# SCH_clavier_2026-02-09.net
KiCad netlist of a schematic drawn in EasyEDA
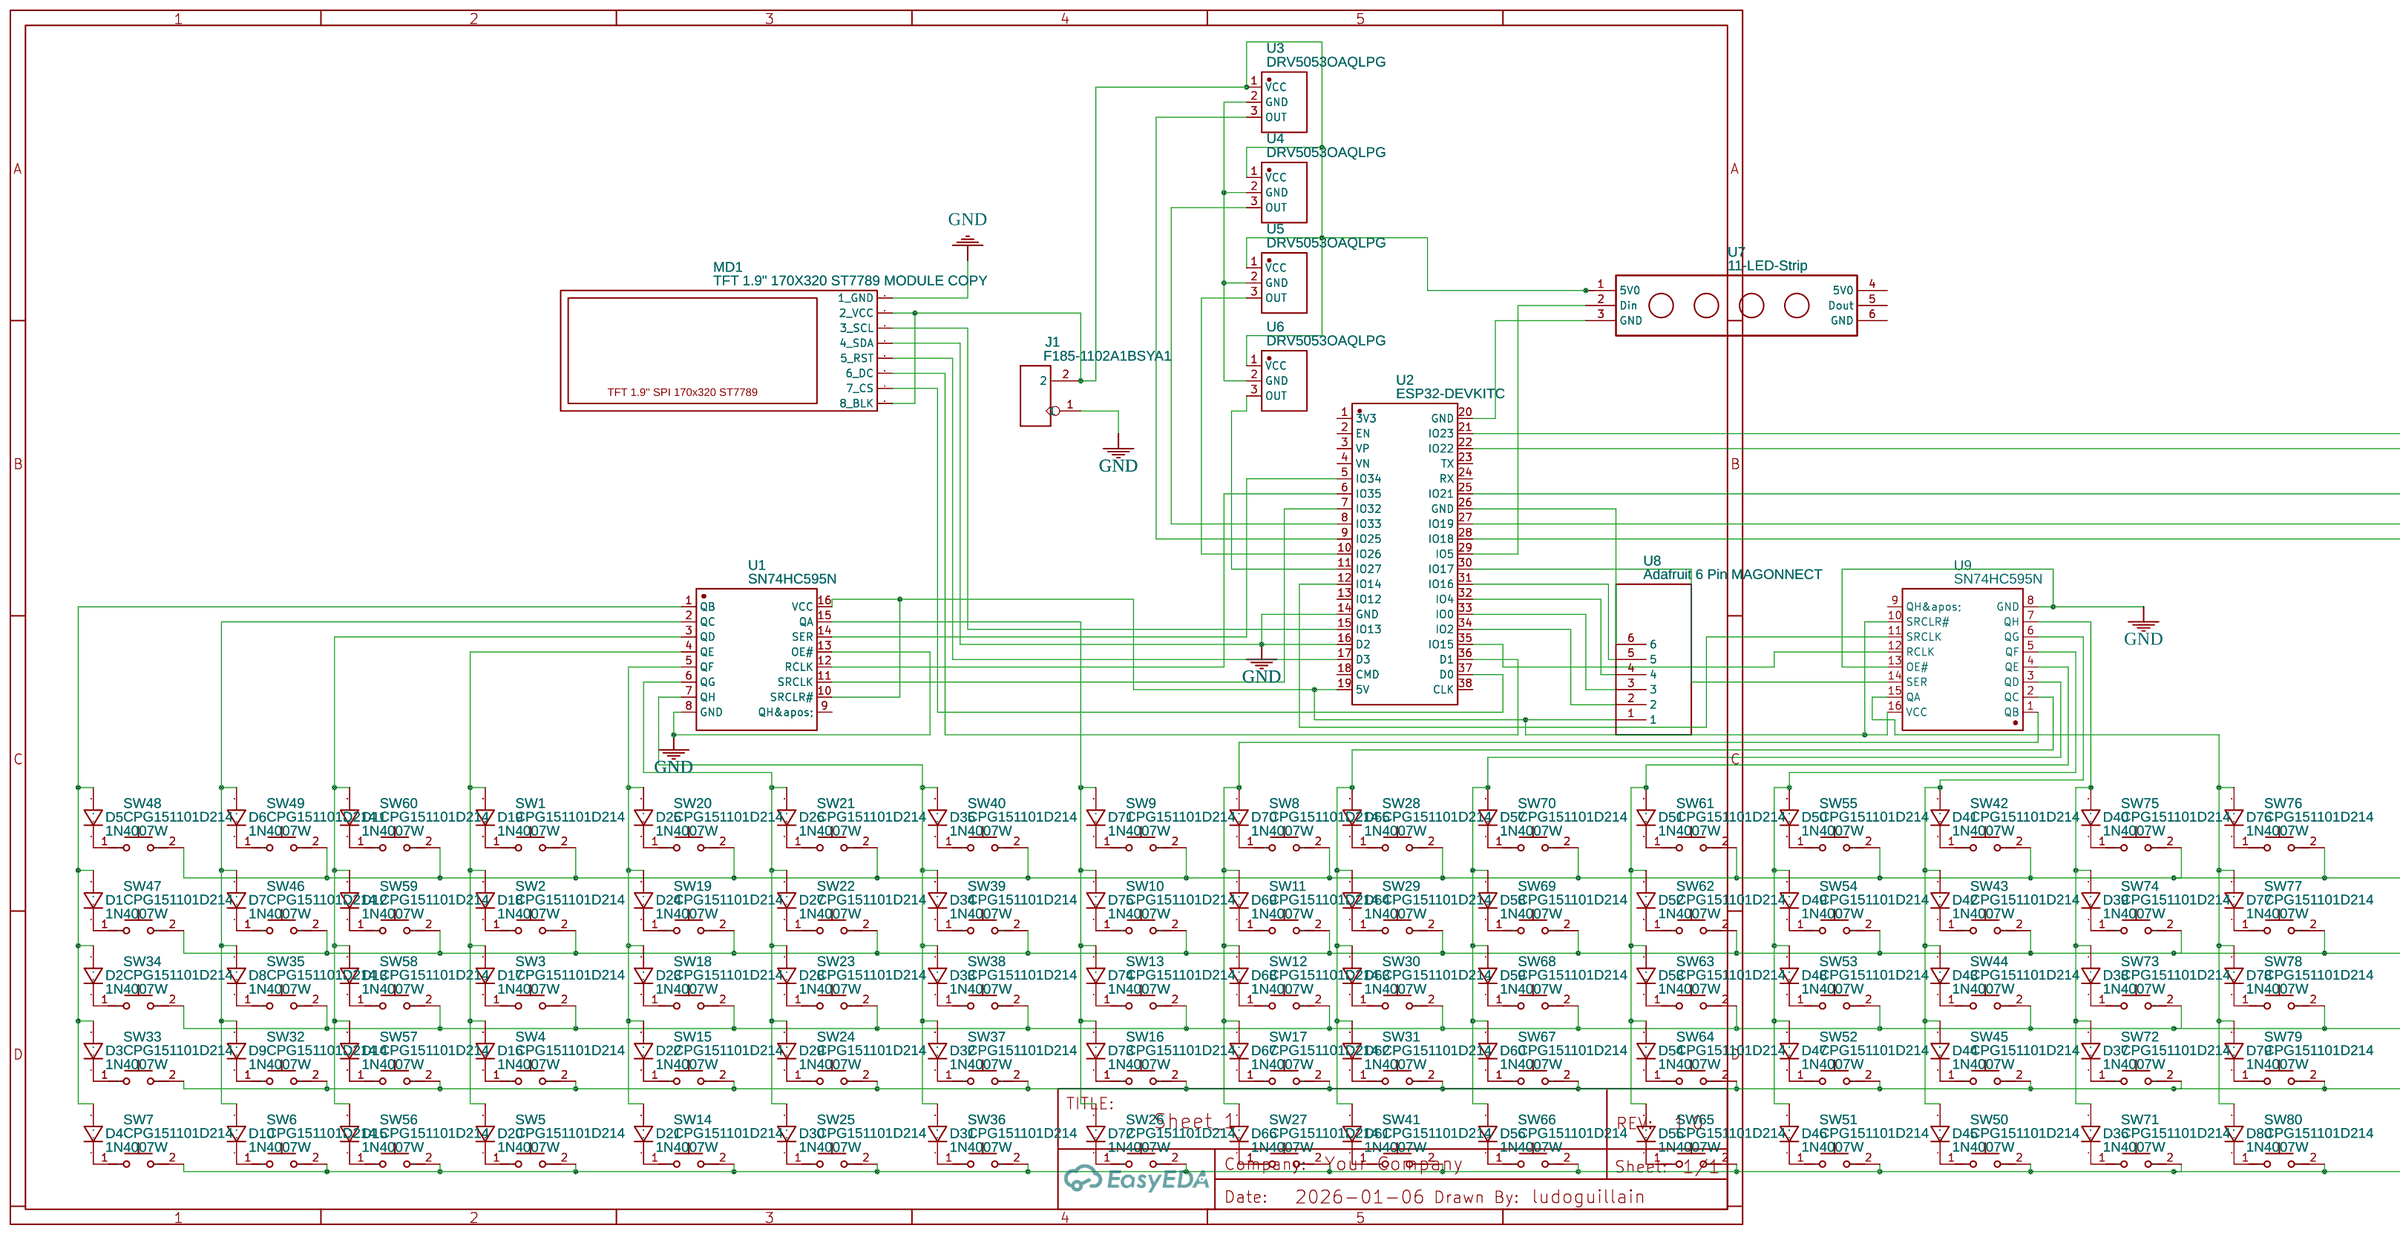
[diagram p0: schematic sheet]

(export (version "E")
  (design (tool "Eeschema 10.0.6"))
  (components
    (comp (ref "D1")
      (value "1N4007W")
      (fields (field (name "Manufacturer") "BLUE ROCKET"))
      (libsource (lib "") (part "1N4007W"))
    )
    (comp (ref "D2")
      (value "1N4007W")
      (fields (field (name "Manufacturer") "BLUE ROCKET"))
      (libsource (lib "") (part "1N4007W"))
    )
    (comp (ref "D3")
      (value "1N4007W")
      (fields (field (name "Manufacturer") "BLUE ROCKET"))
      (libsource (lib "") (part "1N4007W"))
    )
    (comp (ref "D4")
      (value "1N4007W")
      (fields (field (name "Manufacturer") "BLUE ROCKET"))
      (libsource (lib "") (part "1N4007W"))
    )
    (comp (ref "D5")
      (value "1N4007W")
      (fields (field (name "Manufacturer") "BLUE ROCKET"))
      (libsource (lib "") (part "1N4007W"))
    )
    (comp (ref "D6")
      (value "1N4007W")
      (fields (field (name "Manufacturer") "BLUE ROCKET"))
      (libsource (lib "") (part "1N4007W"))
    )
    (comp (ref "D7")
      (value "1N4007W")
      (fields (field (name "Manufacturer") "BLUE ROCKET"))
      (libsource (lib "") (part "1N4007W"))
    )
    (comp (ref "D8")
      (value "1N4007W")
      (fields (field (name "Manufacturer") "BLUE ROCKET"))
      (libsource (lib "") (part "1N4007W"))
    )
    (comp (ref "D9")
      (value "1N4007W")
      (fields (field (name "Manufacturer") "BLUE ROCKET"))
      (libsource (lib "") (part "1N4007W"))
    )
    (comp (ref "D10")
      (value "1N4007W")
      (fields (field (name "Manufacturer") "BLUE ROCKET"))
      (libsource (lib "") (part "1N4007W"))
    )
    (comp (ref "D11")
      (value "1N4007W")
      (fields (field (name "Manufacturer") "BLUE ROCKET"))
      (libsource (lib "") (part "1N4007W"))
    )
    (comp (ref "D12")
      (value "1N4007W")
      (fields (field (name "Manufacturer") "BLUE ROCKET"))
      (libsource (lib "") (part "1N4007W"))
    )
    (comp (ref "D13")
      (value "1N4007W")
      (fields (field (name "Manufacturer") "BLUE ROCKET"))
      (libsource (lib "") (part "1N4007W"))
    )
    (comp (ref "D14")
      (value "1N4007W")
      (fields (field (name "Manufacturer") "BLUE ROCKET"))
      (libsource (lib "") (part "1N4007W"))
    )
    (comp (ref "D15")
      (value "1N4007W")
      (fields (field (name "Manufacturer") "BLUE ROCKET"))
      (libsource (lib "") (part "1N4007W"))
    )
    (comp (ref "D16")
      (value "1N4007W")
      (fields (field (name "Manufacturer") "BLUE ROCKET"))
      (libsource (lib "") (part "1N4007W"))
    )
    (comp (ref "D17")
      (value "1N4007W")
      (fields (field (name "Manufacturer") "BLUE ROCKET"))
      (libsource (lib "") (part "1N4007W"))
    )
    (comp (ref "D18")
      (value "1N4007W")
      (fields (field (name "Manufacturer") "BLUE ROCKET"))
      (libsource (lib "") (part "1N4007W"))
    )
    (comp (ref "D19")
      (value "1N4007W")
      (fields (field (name "Manufacturer") "BLUE ROCKET"))
      (libsource (lib "") (part "1N4007W"))
    )
    (comp (ref "D20")
      (value "1N4007W")
      (fields (field (name "Manufacturer") "BLUE ROCKET"))
      (libsource (lib "") (part "1N4007W"))
    )
    (comp (ref "D21")
      (value "1N4007W")
      (fields (field (name "Manufacturer") "BLUE ROCKET"))
      (libsource (lib "") (part "1N4007W"))
    )
    (comp (ref "D22")
      (value "1N4007W")
      (fields (field (name "Manufacturer") "BLUE ROCKET"))
      (libsource (lib "") (part "1N4007W"))
    )
    (comp (ref "D23")
      (value "1N4007W")
      (fields (field (name "Manufacturer") "BLUE ROCKET"))
      (libsource (lib "") (part "1N4007W"))
    )
    (comp (ref "D24")
      (value "1N4007W")
      (fields (field (name "Manufacturer") "BLUE ROCKET"))
      (libsource (lib "") (part "1N4007W"))
    )
    (comp (ref "D25")
      (value "1N4007W")
      (fields (field (name "Manufacturer") "BLUE ROCKET"))
      (libsource (lib "") (part "1N4007W"))
    )
    (comp (ref "D26")
      (value "1N4007W")
      (fields (field (name "Manufacturer") "BLUE ROCKET"))
      (libsource (lib "") (part "1N4007W"))
    )
    (comp (ref "D27")
      (value "1N4007W")
      (fields (field (name "Manufacturer") "BLUE ROCKET"))
      (libsource (lib "") (part "1N4007W"))
    )
    (comp (ref "D28")
      (value "1N4007W")
      (fields (field (name "Manufacturer") "BLUE ROCKET"))
      (libsource (lib "") (part "1N4007W"))
    )
    (comp (ref "D29")
      (value "1N4007W")
      (fields (field (name "Manufacturer") "BLUE ROCKET"))
      (libsource (lib "") (part "1N4007W"))
    )
    (comp (ref "D30")
      (value "1N4007W")
      (fields (field (name "Manufacturer") "BLUE ROCKET"))
      (libsource (lib "") (part "1N4007W"))
    )
    (comp (ref "D31")
      (value "1N4007W")
      (fields (field (name "Manufacturer") "BLUE ROCKET"))
      (libsource (lib "") (part "1N4007W"))
    )
    (comp (ref "D32")
      (value "1N4007W")
      (fields (field (name "Manufacturer") "BLUE ROCKET"))
      (libsource (lib "") (part "1N4007W"))
    )
    (comp (ref "D33")
      (value "1N4007W")
      (fields (field (name "Manufacturer") "BLUE ROCKET"))
      (libsource (lib "") (part "1N4007W"))
    )
    (comp (ref "D34")
      (value "1N4007W")
      (fields (field (name "Manufacturer") "BLUE ROCKET"))
      (libsource (lib "") (part "1N4007W"))
    )
    (comp (ref "D35")
      (value "1N4007W")
      (fields (field (name "Manufacturer") "BLUE ROCKET"))
      (libsource (lib "") (part "1N4007W"))
    )
    (comp (ref "D36")
      (value "1N4007W")
      (fields (field (name "Manufacturer") "BLUE ROCKET"))
      (libsource (lib "") (part "1N4007W"))
    )
    (comp (ref "D37")
      (value "1N4007W")
      (fields (field (name "Manufacturer") "BLUE ROCKET"))
      (libsource (lib "") (part "1N4007W"))
    )
    (comp (ref "D38")
      (value "1N4007W")
      (fields (field (name "Manufacturer") "BLUE ROCKET"))
      (libsource (lib "") (part "1N4007W"))
    )
    (comp (ref "D39")
      (value "1N4007W")
      (fields (field (name "Manufacturer") "BLUE ROCKET"))
      (libsource (lib "") (part "1N4007W"))
    )
    (comp (ref "D40")
      (value "1N4007W")
      (fields (field (name "Manufacturer") "BLUE ROCKET"))
      (libsource (lib "") (part "1N4007W"))
    )
    (comp (ref "D41")
      (value "1N4007W")
      (fields (field (name "Manufacturer") "BLUE ROCKET"))
      (libsource (lib "") (part "1N4007W"))
    )
    (comp (ref "D42")
      (value "1N4007W")
      (fields (field (name "Manufacturer") "BLUE ROCKET"))
      (libsource (lib "") (part "1N4007W"))
    )
    (comp (ref "D43")
      (value "1N4007W")
      (fields (field (name "Manufacturer") "BLUE ROCKET"))
      (libsource (lib "") (part "1N4007W"))
    )
    (comp (ref "D44")
      (value "1N4007W")
      (fields (field (name "Manufacturer") "BLUE ROCKET"))
      (libsource (lib "") (part "1N4007W"))
    )
    (comp (ref "D45")
      (value "1N4007W")
      (fields (field (name "Manufacturer") "BLUE ROCKET"))
      (libsource (lib "") (part "1N4007W"))
    )
    (comp (ref "D46")
      (value "1N4007W")
      (fields (field (name "Manufacturer") "BLUE ROCKET"))
      (libsource (lib "") (part "1N4007W"))
    )
    (comp (ref "D47")
      (value "1N4007W")
      (fields (field (name "Manufacturer") "BLUE ROCKET"))
      (libsource (lib "") (part "1N4007W"))
    )
    (comp (ref "D48")
      (value "1N4007W")
      (fields (field (name "Manufacturer") "BLUE ROCKET"))
      (libsource (lib "") (part "1N4007W"))
    )
    (comp (ref "D49")
      (value "1N4007W")
      (fields (field (name "Manufacturer") "BLUE ROCKET"))
      (libsource (lib "") (part "1N4007W"))
    )
    (comp (ref "D50")
      (value "1N4007W")
      (fields (field (name "Manufacturer") "BLUE ROCKET"))
      (libsource (lib "") (part "1N4007W"))
    )
    (comp (ref "D51")
      (value "1N4007W")
      (fields (field (name "Manufacturer") "BLUE ROCKET"))
      (libsource (lib "") (part "1N4007W"))
    )
    (comp (ref "D52")
      (value "1N4007W")
      (fields (field (name "Manufacturer") "BLUE ROCKET"))
      (libsource (lib "") (part "1N4007W"))
    )
    (comp (ref "D53")
      (value "1N4007W")
      (fields (field (name "Manufacturer") "BLUE ROCKET"))
      (libsource (lib "") (part "1N4007W"))
    )
    (comp (ref "D54")
      (value "1N4007W")
      (fields (field (name "Manufacturer") "BLUE ROCKET"))
      (libsource (lib "") (part "1N4007W"))
    )
    (comp (ref "D55")
      (value "1N4007W")
      (fields (field (name "Manufacturer") "BLUE ROCKET"))
      (libsource (lib "") (part "1N4007W"))
    )
    (comp (ref "D56")
      (value "1N4007W")
      (fields (field (name "Manufacturer") "BLUE ROCKET"))
      (libsource (lib "") (part "1N4007W"))
    )
    (comp (ref "D57")
      (value "1N4007W")
      (fields (field (name "Manufacturer") "BLUE ROCKET"))
      (libsource (lib "") (part "1N4007W"))
    )
    (comp (ref "D58")
      (value "1N4007W")
      (fields (field (name "Manufacturer") "BLUE ROCKET"))
      (libsource (lib "") (part "1N4007W"))
    )
    (comp (ref "D59")
      (value "1N4007W")
      (fields (field (name "Manufacturer") "BLUE ROCKET"))
      (libsource (lib "") (part "1N4007W"))
    )
    (comp (ref "D60")
      (value "1N4007W")
      (fields (field (name "Manufacturer") "BLUE ROCKET"))
      (libsource (lib "") (part "1N4007W"))
    )
    (comp (ref "D61")
      (value "1N4007W")
      (fields (field (name "Manufacturer") "BLUE ROCKET"))
      (libsource (lib "") (part "1N4007W"))
    )
    (comp (ref "D62")
      (value "1N4007W")
      (fields (field (name "Manufacturer") "BLUE ROCKET"))
      (libsource (lib "") (part "1N4007W"))
    )
    (comp (ref "D63")
      (value "1N4007W")
      (fields (field (name "Manufacturer") "BLUE ROCKET"))
      (libsource (lib "") (part "1N4007W"))
    )
    (comp (ref "D64")
      (value "1N4007W")
      (fields (field (name "Manufacturer") "BLUE ROCKET"))
      (libsource (lib "") (part "1N4007W"))
    )
    (comp (ref "D65")
      (value "1N4007W")
      (fields (field (name "Manufacturer") "BLUE ROCKET"))
      (libsource (lib "") (part "1N4007W"))
    )
    (comp (ref "D66")
      (value "1N4007W")
      (fields (field (name "Manufacturer") "BLUE ROCKET"))
      (libsource (lib "") (part "1N4007W"))
    )
    (comp (ref "D67")
      (value "1N4007W")
      (fields (field (name "Manufacturer") "BLUE ROCKET"))
      (libsource (lib "") (part "1N4007W"))
    )
    (comp (ref "D68")
      (value "1N4007W")
      (fields (field (name "Manufacturer") "BLUE ROCKET"))
      (libsource (lib "") (part "1N4007W"))
    )
    (comp (ref "D69")
      (value "1N4007W")
      (fields (field (name "Manufacturer") "BLUE ROCKET"))
      (libsource (lib "") (part "1N4007W"))
    )
    (comp (ref "D70")
      (value "1N4007W")
      (fields (field (name "Manufacturer") "BLUE ROCKET"))
      (libsource (lib "") (part "1N4007W"))
    )
    (comp (ref "D71")
      (value "1N4007W")
      (fields (field (name "Manufacturer") "BLUE ROCKET"))
      (libsource (lib "") (part "1N4007W"))
    )
    (comp (ref "D72")
      (value "1N4007W")
      (fields (field (name "Manufacturer") "BLUE ROCKET"))
      (libsource (lib "") (part "1N4007W"))
    )
    (comp (ref "D73")
      (value "1N4007W")
      (fields (field (name "Manufacturer") "BLUE ROCKET"))
      (libsource (lib "") (part "1N4007W"))
    )
    (comp (ref "D74")
      (value "1N4007W")
      (fields (field (name "Manufacturer") "BLUE ROCKET"))
      (libsource (lib "") (part "1N4007W"))
    )
    (comp (ref "D75")
      (value "1N4007W")
      (fields (field (name "Manufacturer") "BLUE ROCKET"))
      (libsource (lib "") (part "1N4007W"))
    )
    (comp (ref "D76")
      (value "1N4007W")
      (fields (field (name "Manufacturer") "BLUE ROCKET"))
      (libsource (lib "") (part "1N4007W"))
    )
    (comp (ref "D77")
      (value "1N4007W")
      (fields (field (name "Manufacturer") "BLUE ROCKET"))
      (libsource (lib "") (part "1N4007W"))
    )
    (comp (ref "D78")
      (value "1N4007W")
      (fields (field (name "Manufacturer") "BLUE ROCKET"))
      (libsource (lib "") (part "1N4007W"))
    )
    (comp (ref "D79")
      (value "1N4007W")
      (fields (field (name "Manufacturer") "BLUE ROCKET"))
      (libsource (lib "") (part "1N4007W"))
    )
    (comp (ref "D80")
      (value "1N4007W")
      (fields (field (name "Manufacturer") "BLUE ROCKET"))
      (libsource (lib "") (part "1N4007W"))
    )
    (comp (ref "J1") (value "F185-1102A1BSYA1") (libsource (lib "") (part "F185-1102A1BSYA1")))
    (comp (ref "MD1")
      (value "TFT 1.9\" 170X320 ST7789 MODULE COPY")
      (libsource (lib "") (part "TFT 1.9{dblquote} 170X320 ST7789 MODULE COPY"))
    )
    (comp (ref "SW1")
      (value "CPG151101D214")
      (fields (field (name "Manufacturer") "Kailh(凯华)"))
      (libsource (lib "") (part "CPG151101D214"))
    )
    (comp (ref "SW2")
      (value "CPG151101D214")
      (fields (field (name "Manufacturer") "Kailh(凯华)"))
      (libsource (lib "") (part "CPG151101D214"))
    )
    (comp (ref "SW3")
      (value "CPG151101D214")
      (fields (field (name "Manufacturer") "Kailh(凯华)"))
      (libsource (lib "") (part "CPG151101D214"))
    )
    (comp (ref "SW4")
      (value "CPG151101D214")
      (fields (field (name "Manufacturer") "Kailh(凯华)"))
      (libsource (lib "") (part "CPG151101D214"))
    )
    (comp (ref "SW5")
      (value "CPG151101D214")
      (fields (field (name "Manufacturer") "Kailh(凯华)"))
      (libsource (lib "") (part "CPG151101D214"))
    )
    (comp (ref "SW6")
      (value "CPG151101D214")
      (fields (field (name "Manufacturer") "Kailh(凯华)"))
      (libsource (lib "") (part "CPG151101D214"))
    )
    (comp (ref "SW7")
      (value "CPG151101D214")
      (fields (field (name "Manufacturer") "Kailh(凯华)"))
      (libsource (lib "") (part "CPG151101D214"))
    )
    (comp (ref "SW8")
      (value "CPG151101D214")
      (fields (field (name "Manufacturer") "Kailh(凯华)"))
      (libsource (lib "") (part "CPG151101D214"))
    )
    (comp (ref "SW9")
      (value "CPG151101D214")
      (fields (field (name "Manufacturer") "Kailh(凯华)"))
      (libsource (lib "") (part "CPG151101D214"))
    )
    (comp (ref "SW10")
      (value "CPG151101D214")
      (fields (field (name "Manufacturer") "Kailh(凯华)"))
      (libsource (lib "") (part "CPG151101D214"))
    )
    (comp (ref "SW11")
      (value "CPG151101D214")
      (fields (field (name "Manufacturer") "Kailh(凯华)"))
      (libsource (lib "") (part "CPG151101D214"))
    )
    (comp (ref "SW12")
      (value "CPG151101D214")
      (fields (field (name "Manufacturer") "Kailh(凯华)"))
      (libsource (lib "") (part "CPG151101D214"))
    )
    (comp (ref "SW13")
      (value "CPG151101D214")
      (fields (field (name "Manufacturer") "Kailh(凯华)"))
      (libsource (lib "") (part "CPG151101D214"))
    )
    (comp (ref "SW14")
      (value "CPG151101D214")
      (fields (field (name "Manufacturer") "Kailh(凯华)"))
      (libsource (lib "") (part "CPG151101D214"))
    )
    (comp (ref "SW15")
      (value "CPG151101D214")
      (fields (field (name "Manufacturer") "Kailh(凯华)"))
      (libsource (lib "") (part "CPG151101D214"))
    )
    (comp (ref "SW16")
      (value "CPG151101D214")
      (fields (field (name "Manufacturer") "Kailh(凯华)"))
      (libsource (lib "") (part "CPG151101D214"))
    )
    (comp (ref "SW17")
      (value "CPG151101D214")
      (fields (field (name "Manufacturer") "Kailh(凯华)"))
      (libsource (lib "") (part "CPG151101D214"))
    )
    (comp (ref "SW18")
      (value "CPG151101D214")
      (fields (field (name "Manufacturer") "Kailh(凯华)"))
      (libsource (lib "") (part "CPG151101D214"))
    )
    (comp (ref "SW19")
      (value "CPG151101D214")
      (fields (field (name "Manufacturer") "Kailh(凯华)"))
      (libsource (lib "") (part "CPG151101D214"))
    )
    (comp (ref "SW20")
      (value "CPG151101D214")
      (fields (field (name "Manufacturer") "Kailh(凯华)"))
      (libsource (lib "") (part "CPG151101D214"))
    )
    (comp (ref "SW21")
      (value "CPG151101D214")
      (fields (field (name "Manufacturer") "Kailh(凯华)"))
      (libsource (lib "") (part "CPG151101D214"))
    )
    (comp (ref "SW22")
      (value "CPG151101D214")
      (fields (field (name "Manufacturer") "Kailh(凯华)"))
      (libsource (lib "") (part "CPG151101D214"))
    )
    (comp (ref "SW23")
      (value "CPG151101D214")
      (fields (field (name "Manufacturer") "Kailh(凯华)"))
      (libsource (lib "") (part "CPG151101D214"))
    )
    (comp (ref "SW24")
      (value "CPG151101D214")
      (fields (field (name "Manufacturer") "Kailh(凯华)"))
      (libsource (lib "") (part "CPG151101D214"))
    )
    (comp (ref "SW25")
      (value "CPG151101D214")
      (fields (field (name "Manufacturer") "Kailh(凯华)"))
      (libsource (lib "") (part "CPG151101D214"))
    )
    (comp (ref "SW26")
      (value "CPG151101D214")
      (fields (field (name "Manufacturer") "Kailh(凯华)"))
      (libsource (lib "") (part "CPG151101D214"))
    )
    (comp (ref "SW27")
      (value "CPG151101D214")
      (fields (field (name "Manufacturer") "Kailh(凯华)"))
      (libsource (lib "") (part "CPG151101D214"))
    )
    (comp (ref "SW28")
      (value "CPG151101D214")
      (fields (field (name "Manufacturer") "Kailh(凯华)"))
      (libsource (lib "") (part "CPG151101D214"))
    )
    (comp (ref "SW29")
      (value "CPG151101D214")
      (fields (field (name "Manufacturer") "Kailh(凯华)"))
      (libsource (lib "") (part "CPG151101D214"))
    )
    (comp (ref "SW30")
      (value "CPG151101D214")
      (fields (field (name "Manufacturer") "Kailh(凯华)"))
      (libsource (lib "") (part "CPG151101D214"))
    )
    (comp (ref "SW31")
      (value "CPG151101D214")
      (fields (field (name "Manufacturer") "Kailh(凯华)"))
      (libsource (lib "") (part "CPG151101D214"))
    )
    (comp (ref "SW32")
      (value "CPG151101D214")
      (fields (field (name "Manufacturer") "Kailh(凯华)"))
      (libsource (lib "") (part "CPG151101D214"))
    )
    (comp (ref "SW33")
      (value "CPG151101D214")
      (fields (field (name "Manufacturer") "Kailh(凯华)"))
      (libsource (lib "") (part "CPG151101D214"))
    )
    (comp (ref "SW34")
      (value "CPG151101D214")
      (fields (field (name "Manufacturer") "Kailh(凯华)"))
      (libsource (lib "") (part "CPG151101D214"))
    )
    (comp (ref "SW35")
      (value "CPG151101D214")
      (fields (field (name "Manufacturer") "Kailh(凯华)"))
      (libsource (lib "") (part "CPG151101D214"))
    )
    (comp (ref "SW36")
      (value "CPG151101D214")
      (fields (field (name "Manufacturer") "Kailh(凯华)"))
      (libsource (lib "") (part "CPG151101D214"))
    )
    (comp (ref "SW37")
      (value "CPG151101D214")
      (fields (field (name "Manufacturer") "Kailh(凯华)"))
      (libsource (lib "") (part "CPG151101D214"))
    )
    (comp (ref "SW38")
      (value "CPG151101D214")
      (fields (field (name "Manufacturer") "Kailh(凯华)"))
      (libsource (lib "") (part "CPG151101D214"))
    )
    (comp (ref "SW39")
      (value "CPG151101D214")
      (fields (field (name "Manufacturer") "Kailh(凯华)"))
      (libsource (lib "") (part "CPG151101D214"))
    )
    (comp (ref "SW40")
      (value "CPG151101D214")
      (fields (field (name "Manufacturer") "Kailh(凯华)"))
      (libsource (lib "") (part "CPG151101D214"))
    )
    (comp (ref "SW41")
      (value "CPG151101D214")
      (fields (field (name "Manufacturer") "Kailh(凯华)"))
      (libsource (lib "") (part "CPG151101D214"))
    )
    (comp (ref "SW42")
      (value "CPG151101D214")
      (fields (field (name "Manufacturer") "Kailh(凯华)"))
      (libsource (lib "") (part "CPG151101D214"))
    )
    (comp (ref "SW43")
      (value "CPG151101D214")
      (fields (field (name "Manufacturer") "Kailh(凯华)"))
      (libsource (lib "") (part "CPG151101D214"))
    )
    (comp (ref "SW44")
      (value "CPG151101D214")
      (fields (field (name "Manufacturer") "Kailh(凯华)"))
      (libsource (lib "") (part "CPG151101D214"))
    )
    (comp (ref "SW45")
      (value "CPG151101D214")
      (fields (field (name "Manufacturer") "Kailh(凯华)"))
      (libsource (lib "") (part "CPG151101D214"))
    )
    (comp (ref "SW46")
      (value "CPG151101D214")
      (fields (field (name "Manufacturer") "Kailh(凯华)"))
      (libsource (lib "") (part "CPG151101D214"))
    )
    (comp (ref "SW47")
      (value "CPG151101D214")
      (fields (field (name "Manufacturer") "Kailh(凯华)"))
      (libsource (lib "") (part "CPG151101D214"))
    )
    (comp (ref "SW48")
      (value "CPG151101D214")
      (fields (field (name "Manufacturer") "Kailh(凯华)"))
      (libsource (lib "") (part "CPG151101D214"))
    )
    (comp (ref "SW49")
      (value "CPG151101D214")
      (fields (field (name "Manufacturer") "Kailh(凯华)"))
      (libsource (lib "") (part "CPG151101D214"))
    )
    (comp (ref "SW50")
      (value "CPG151101D214")
      (fields (field (name "Manufacturer") "Kailh(凯华)"))
      (libsource (lib "") (part "CPG151101D214"))
    )
    (comp (ref "SW51")
      (value "CPG151101D214")
      (fields (field (name "Manufacturer") "Kailh(凯华)"))
      (libsource (lib "") (part "CPG151101D214"))
    )
    (comp (ref "SW52")
      (value "CPG151101D214")
      (fields (field (name "Manufacturer") "Kailh(凯华)"))
      (libsource (lib "") (part "CPG151101D214"))
    )
    (comp (ref "SW53")
      (value "CPG151101D214")
      (fields (field (name "Manufacturer") "Kailh(凯华)"))
      (libsource (lib "") (part "CPG151101D214"))
    )
    (comp (ref "SW54")
      (value "CPG151101D214")
      (fields (field (name "Manufacturer") "Kailh(凯华)"))
      (libsource (lib "") (part "CPG151101D214"))
    )
    (comp (ref "SW55")
      (value "CPG151101D214")
      (fields (field (name "Manufacturer") "Kailh(凯华)"))
      (libsource (lib "") (part "CPG151101D214"))
    )
    (comp (ref "SW56")
      (value "CPG151101D214")
      (fields (field (name "Manufacturer") "Kailh(凯华)"))
      (libsource (lib "") (part "CPG151101D214"))
    )
    (comp (ref "SW57")
      (value "CPG151101D214")
      (fields (field (name "Manufacturer") "Kailh(凯华)"))
      (libsource (lib "") (part "CPG151101D214"))
    )
    (comp (ref "SW58")
      (value "CPG151101D214")
      (fields (field (name "Manufacturer") "Kailh(凯华)"))
      (libsource (lib "") (part "CPG151101D214"))
    )
    (comp (ref "SW59")
      (value "CPG151101D214")
      (fields (field (name "Manufacturer") "Kailh(凯华)"))
      (libsource (lib "") (part "CPG151101D214"))
    )
    (comp (ref "SW60")
      (value "CPG151101D214")
      (fields (field (name "Manufacturer") "Kailh(凯华)"))
      (libsource (lib "") (part "CPG151101D214"))
    )
    (comp (ref "SW61")
      (value "CPG151101D214")
      (fields (field (name "Manufacturer") "Kailh(凯华)"))
      (libsource (lib "") (part "CPG151101D214"))
    )
    (comp (ref "SW62")
      (value "CPG151101D214")
      (fields (field (name "Manufacturer") "Kailh(凯华)"))
      (libsource (lib "") (part "CPG151101D214"))
    )
    (comp (ref "SW63")
      (value "CPG151101D214")
      (fields (field (name "Manufacturer") "Kailh(凯华)"))
      (libsource (lib "") (part "CPG151101D214"))
    )
    (comp (ref "SW64")
      (value "CPG151101D214")
      (fields (field (name "Manufacturer") "Kailh(凯华)"))
      (libsource (lib "") (part "CPG151101D214"))
    )
    (comp (ref "SW65")
      (value "CPG151101D214")
      (fields (field (name "Manufacturer") "Kailh(凯华)"))
      (libsource (lib "") (part "CPG151101D214"))
    )
    (comp (ref "SW66")
      (value "CPG151101D214")
      (fields (field (name "Manufacturer") "Kailh(凯华)"))
      (libsource (lib "") (part "CPG151101D214"))
    )
    (comp (ref "SW67")
      (value "CPG151101D214")
      (fields (field (name "Manufacturer") "Kailh(凯华)"))
      (libsource (lib "") (part "CPG151101D214"))
    )
    (comp (ref "SW68")
      (value "CPG151101D214")
      (fields (field (name "Manufacturer") "Kailh(凯华)"))
      (libsource (lib "") (part "CPG151101D214"))
    )
    (comp (ref "SW69")
      (value "CPG151101D214")
      (fields (field (name "Manufacturer") "Kailh(凯华)"))
      (libsource (lib "") (part "CPG151101D214"))
    )
    (comp (ref "SW70")
      (value "CPG151101D214")
      (fields (field (name "Manufacturer") "Kailh(凯华)"))
      (libsource (lib "") (part "CPG151101D214"))
    )
    (comp (ref "SW71")
      (value "CPG151101D214")
      (fields (field (name "Manufacturer") "Kailh(凯华)"))
      (libsource (lib "") (part "CPG151101D214"))
    )
    (comp (ref "SW72")
      (value "CPG151101D214")
      (fields (field (name "Manufacturer") "Kailh(凯华)"))
      (libsource (lib "") (part "CPG151101D214"))
    )
    (comp (ref "SW73")
      (value "CPG151101D214")
      (fields (field (name "Manufacturer") "Kailh(凯华)"))
      (libsource (lib "") (part "CPG151101D214"))
    )
    (comp (ref "SW74")
      (value "CPG151101D214")
      (fields (field (name "Manufacturer") "Kailh(凯华)"))
      (libsource (lib "") (part "CPG151101D214"))
    )
    (comp (ref "SW75")
      (value "CPG151101D214")
      (fields (field (name "Manufacturer") "Kailh(凯华)"))
      (libsource (lib "") (part "CPG151101D214"))
    )
    (comp (ref "SW76")
      (value "CPG151101D214")
      (fields (field (name "Manufacturer") "Kailh(凯华)"))
      (libsource (lib "") (part "CPG151101D214"))
    )
    (comp (ref "SW77")
      (value "CPG151101D214")
      (fields (field (name "Manufacturer") "Kailh(凯华)"))
      (libsource (lib "") (part "CPG151101D214"))
    )
    (comp (ref "SW78")
      (value "CPG151101D214")
      (fields (field (name "Manufacturer") "Kailh(凯华)"))
      (libsource (lib "") (part "CPG151101D214"))
    )
    (comp (ref "SW79")
      (value "CPG151101D214")
      (fields (field (name "Manufacturer") "Kailh(凯华)"))
      (libsource (lib "") (part "CPG151101D214"))
    )
    (comp (ref "SW80")
      (value "CPG151101D214")
      (fields (field (name "Manufacturer") "Kailh(凯华)"))
      (libsource (lib "") (part "CPG151101D214"))
    )
    (comp (ref "U1")
      (value "SN74HC595N")
      (fields (field (name "Manufacturer") "TI(德州仪器)"))
      (libsource (lib "") (part "SN74HC595N_1"))
    )
    (comp (ref "U2")
      (value "ESP32-DEVKITC")
      (fields
        (field (name "Manufacturer Part") "ESP32-DevKitC")
        (field (name "Manufacturer") "ESPRESSIF(乐鑫)")
      )
      (libsource (lib "") (part "ESP32-DEVKITC"))
    )
    (comp (ref "U3")
      (value "DRV5053OAQLPG")
      (fields (field (name "Manufacturer") "TI(德州仪器)"))
      (libsource (lib "") (part "DRV5053OAQLPG"))
    )
    (comp (ref "U4")
      (value "DRV5053OAQLPG")
      (fields (field (name "Manufacturer") "TI(德州仪器)"))
      (libsource (lib "") (part "DRV5053OAQLPG"))
    )
    (comp (ref "U5")
      (value "DRV5053OAQLPG")
      (fields (field (name "Manufacturer") "TI(德州仪器)"))
      (libsource (lib "") (part "DRV5053OAQLPG"))
    )
    (comp (ref "U6")
      (value "DRV5053OAQLPG")
      (fields (field (name "Manufacturer") "TI(德州仪器)"))
      (libsource (lib "") (part "DRV5053OAQLPG"))
    )
    (comp (ref "U7") (value "11-LED-Strip") (libsource (lib "") (part "11-LED-Strip")))
    (comp (ref "U8")
      (value "Adafruit 6 Pin MAGONNECT")
      (libsource (lib "") (part "Adafruit 6 Pin MAGONNECT"))
    )
    (comp (ref "U9")
      (value "SN74HC595N")
      (fields (field (name "Manufacturer") "TI(德州仪器)"))
      (libsource (lib "") (part "SN74HC595N"))
    )
  )
  (nets
    (net (code "1") (name "GND") (class "Default")
      (node (ref "J1") (pin "1") (pinfunction "1_1") (pintype "unspecified"))
      (node (ref "MD1") (pin "1") (pinfunction "1_GND_1") (pintype "unspecified"))
      (node (ref "MD1") (pin "4") (pinfunction "4_SDA_4") (pintype "unspecified"))
      (node (ref "U1") (pin "13") (pinfunction "OE#_13") (pintype "unspecified"))
      (node (ref "U1") (pin "8") (pinfunction "GND_8") (pintype "unspecified"))
      (node (ref "U2") (pin "14") (pinfunction "GND_14") (pintype "unspecified"))
      (node (ref "U2") (pin "16") (pinfunction "D2_16") (pintype "unspecified"))
      (node (ref "U9") (pin "13") (pinfunction "OE#_13") (pintype "unspecified"))
      (node (ref "U9") (pin "8") (pinfunction "GND_8") (pintype "unspecified"))
    )
    (net (code "2") (name "Net-(D1-Pad1)") (class "Default")
      (node (ref "D1") (pin "1") (pinfunction "1_1") (pintype "unspecified"))
      (node (ref "SW47") (pin "1") (pinfunction "1_1") (pintype "unspecified"))
    )
    (net (code "3") (name "Net-(D2-Pad1)") (class "Default")
      (node (ref "D2") (pin "1") (pinfunction "1_1") (pintype "unspecified"))
      (node (ref "SW34") (pin "1") (pinfunction "1_1") (pintype "unspecified"))
    )
    (net (code "4") (name "Net-(D3-Pad1)") (class "Default")
      (node (ref "D3") (pin "1") (pinfunction "1_1") (pintype "unspecified"))
      (node (ref "SW33") (pin "1") (pinfunction "1_1") (pintype "unspecified"))
    )
    (net (code "5") (name "Net-(D4-Pad1)") (class "Default")
      (node (ref "D4") (pin "1") (pinfunction "1_1") (pintype "unspecified"))
      (node (ref "SW7") (pin "1") (pinfunction "1_1") (pintype "unspecified"))
    )
    (net (code "6") (name "Net-(D5-Pad1)") (class "Default")
      (node (ref "D5") (pin "1") (pinfunction "1_1") (pintype "unspecified"))
      (node (ref "SW48") (pin "1") (pinfunction "1_1") (pintype "unspecified"))
    )
    (net (code "7") (name "Net-(D6-Pad1)") (class "Default")
      (node (ref "D6") (pin "1") (pinfunction "1_1") (pintype "unspecified"))
      (node (ref "SW49") (pin "1") (pinfunction "1_1") (pintype "unspecified"))
    )
    (net (code "8") (name "Net-(D7-Pad1)") (class "Default")
      (node (ref "D7") (pin "1") (pinfunction "1_1") (pintype "unspecified"))
      (node (ref "SW46") (pin "1") (pinfunction "1_1") (pintype "unspecified"))
    )
    (net (code "9") (name "Net-(D8-Pad1)") (class "Default")
      (node (ref "D8") (pin "1") (pinfunction "1_1") (pintype "unspecified"))
      (node (ref "SW35") (pin "1") (pinfunction "1_1") (pintype "unspecified"))
    )
    (net (code "10") (name "Net-(D9-Pad1)") (class "Default")
      (node (ref "D9") (pin "1") (pinfunction "1_1") (pintype "unspecified"))
      (node (ref "SW32") (pin "1") (pinfunction "1_1") (pintype "unspecified"))
    )
    (net (code "11") (name "Net-(D10-Pad1)") (class "Default")
      (node (ref "D10") (pin "1") (pinfunction "1_1") (pintype "unspecified"))
      (node (ref "SW6") (pin "1") (pinfunction "1_1") (pintype "unspecified"))
    )
    (net (code "12") (name "Net-(D11-Pad1)") (class "Default")
      (node (ref "D11") (pin "1") (pinfunction "1_1") (pintype "unspecified"))
      (node (ref "SW60") (pin "1") (pinfunction "1_1") (pintype "unspecified"))
    )
    (net (code "13") (name "Net-(D12-Pad1)") (class "Default")
      (node (ref "D12") (pin "1") (pinfunction "1_1") (pintype "unspecified"))
      (node (ref "SW59") (pin "1") (pinfunction "1_1") (pintype "unspecified"))
    )
    (net (code "14") (name "Net-(D13-Pad1)") (class "Default")
      (node (ref "D13") (pin "1") (pinfunction "1_1") (pintype "unspecified"))
      (node (ref "SW58") (pin "1") (pinfunction "1_1") (pintype "unspecified"))
    )
    (net (code "15") (name "Net-(D14-Pad1)") (class "Default")
      (node (ref "D14") (pin "1") (pinfunction "1_1") (pintype "unspecified"))
      (node (ref "SW57") (pin "1") (pinfunction "1_1") (pintype "unspecified"))
    )
    (net (code "16") (name "Net-(D15-Pad1)") (class "Default")
      (node (ref "D15") (pin "1") (pinfunction "1_1") (pintype "unspecified"))
      (node (ref "SW56") (pin "1") (pinfunction "1_1") (pintype "unspecified"))
    )
    (net (code "17") (name "Net-(D16-Pad1)") (class "Default")
      (node (ref "D16") (pin "1") (pinfunction "1_1") (pintype "unspecified"))
      (node (ref "SW4") (pin "1") (pinfunction "1_1") (pintype "unspecified"))
    )
    (net (code "18") (name "Net-(D17-Pad1)") (class "Default")
      (node (ref "D17") (pin "1") (pinfunction "1_1") (pintype "unspecified"))
      (node (ref "SW3") (pin "1") (pinfunction "1_1") (pintype "unspecified"))
    )
    (net (code "19") (name "Net-(D18-Pad1)") (class "Default")
      (node (ref "D18") (pin "1") (pinfunction "1_1") (pintype "unspecified"))
      (node (ref "SW2") (pin "1") (pinfunction "1_1") (pintype "unspecified"))
    )
    (net (code "20") (name "Net-(D19-Pad1)") (class "Default")
      (node (ref "D19") (pin "1") (pinfunction "1_1") (pintype "unspecified"))
      (node (ref "SW1") (pin "1") (pinfunction "1_1") (pintype "unspecified"))
    )
    (net (code "21") (name "Net-(D20-Pad1)") (class "Default")
      (node (ref "D20") (pin "1") (pinfunction "1_1") (pintype "unspecified"))
      (node (ref "SW5") (pin "1") (pinfunction "1_1") (pintype "unspecified"))
    )
    (net (code "22") (name "Net-(D21-Pad1)") (class "Default")
      (node (ref "D21") (pin "1") (pinfunction "1_1") (pintype "unspecified"))
      (node (ref "SW14") (pin "1") (pinfunction "1_1") (pintype "unspecified"))
    )
    (net (code "23") (name "Net-(D22-Pad1)") (class "Default")
      (node (ref "D22") (pin "1") (pinfunction "1_1") (pintype "unspecified"))
      (node (ref "SW15") (pin "1") (pinfunction "1_1") (pintype "unspecified"))
    )
    (net (code "24") (name "Net-(D23-Pad1)") (class "Default")
      (node (ref "D23") (pin "1") (pinfunction "1_1") (pintype "unspecified"))
      (node (ref "SW18") (pin "1") (pinfunction "1_1") (pintype "unspecified"))
    )
    (net (code "25") (name "Net-(D24-Pad1)") (class "Default")
      (node (ref "D24") (pin "1") (pinfunction "1_1") (pintype "unspecified"))
      (node (ref "SW19") (pin "1") (pinfunction "1_1") (pintype "unspecified"))
    )
    (net (code "26") (name "Net-(D25-Pad1)") (class "Default")
      (node (ref "D25") (pin "1") (pinfunction "1_1") (pintype "unspecified"))
      (node (ref "SW20") (pin "1") (pinfunction "1_1") (pintype "unspecified"))
    )
    (net (code "27") (name "Net-(D26-Pad1)") (class "Default")
      (node (ref "D26") (pin "1") (pinfunction "1_1") (pintype "unspecified"))
      (node (ref "SW21") (pin "1") (pinfunction "1_1") (pintype "unspecified"))
    )
    (net (code "28") (name "Net-(D27-Pad1)") (class "Default")
      (node (ref "D27") (pin "1") (pinfunction "1_1") (pintype "unspecified"))
      (node (ref "SW22") (pin "1") (pinfunction "1_1") (pintype "unspecified"))
    )
    (net (code "29") (name "Net-(D28-Pad1)") (class "Default")
      (node (ref "D28") (pin "1") (pinfunction "1_1") (pintype "unspecified"))
      (node (ref "SW23") (pin "1") (pinfunction "1_1") (pintype "unspecified"))
    )
    (net (code "30") (name "Net-(D29-Pad1)") (class "Default")
      (node (ref "D29") (pin "1") (pinfunction "1_1") (pintype "unspecified"))
      (node (ref "SW24") (pin "1") (pinfunction "1_1") (pintype "unspecified"))
    )
    (net (code "31") (name "Net-(D30-Pad1)") (class "Default")
      (node (ref "D30") (pin "1") (pinfunction "1_1") (pintype "unspecified"))
      (node (ref "SW25") (pin "1") (pinfunction "1_1") (pintype "unspecified"))
    )
    (net (code "32") (name "Net-(D31-Pad1)") (class "Default")
      (node (ref "D31") (pin "1") (pinfunction "1_1") (pintype "unspecified"))
      (node (ref "SW36") (pin "1") (pinfunction "1_1") (pintype "unspecified"))
    )
    (net (code "33") (name "Net-(D32-Pad1)") (class "Default")
      (node (ref "D32") (pin "1") (pinfunction "1_1") (pintype "unspecified"))
      (node (ref "SW37") (pin "1") (pinfunction "1_1") (pintype "unspecified"))
    )
    (net (code "34") (name "Net-(D33-Pad1)") (class "Default")
      (node (ref "D33") (pin "1") (pinfunction "1_1") (pintype "unspecified"))
      (node (ref "SW38") (pin "1") (pinfunction "1_1") (pintype "unspecified"))
    )
    (net (code "35") (name "Net-(D34-Pad1)") (class "Default")
      (node (ref "D34") (pin "1") (pinfunction "1_1") (pintype "unspecified"))
      (node (ref "SW39") (pin "1") (pinfunction "1_1") (pintype "unspecified"))
    )
    (net (code "36") (name "Net-(D35-Pad1)") (class "Default")
      (node (ref "D35") (pin "1") (pinfunction "1_1") (pintype "unspecified"))
      (node (ref "SW40") (pin "1") (pinfunction "1_1") (pintype "unspecified"))
    )
    (net (code "37") (name "Net-(D36-Pad1)") (class "Default")
      (node (ref "D36") (pin "1") (pinfunction "1_1") (pintype "unspecified"))
      (node (ref "SW71") (pin "1") (pinfunction "1_1") (pintype "unspecified"))
    )
    (net (code "38") (name "Net-(D37-Pad1)") (class "Default")
      (node (ref "D37") (pin "1") (pinfunction "1_1") (pintype "unspecified"))
      (node (ref "SW72") (pin "1") (pinfunction "1_1") (pintype "unspecified"))
    )
    (net (code "39") (name "Net-(D38-Pad1)") (class "Default")
      (node (ref "D38") (pin "1") (pinfunction "1_1") (pintype "unspecified"))
      (node (ref "SW73") (pin "1") (pinfunction "1_1") (pintype "unspecified"))
    )
    (net (code "40") (name "Net-(D39-Pad1)") (class "Default")
      (node (ref "D39") (pin "1") (pinfunction "1_1") (pintype "unspecified"))
      (node (ref "SW74") (pin "1") (pinfunction "1_1") (pintype "unspecified"))
    )
    (net (code "41") (name "Net-(D40-Pad1)") (class "Default")
      (node (ref "D40") (pin "1") (pinfunction "1_1") (pintype "unspecified"))
      (node (ref "SW75") (pin "1") (pinfunction "1_1") (pintype "unspecified"))
    )
    (net (code "42") (name "Net-(D41-Pad1)") (class "Default")
      (node (ref "D41") (pin "1") (pinfunction "1_1") (pintype "unspecified"))
      (node (ref "SW42") (pin "1") (pinfunction "1_1") (pintype "unspecified"))
    )
    (net (code "43") (name "Net-(D42-Pad1)") (class "Default")
      (node (ref "D42") (pin "1") (pinfunction "1_1") (pintype "unspecified"))
      (node (ref "SW43") (pin "1") (pinfunction "1_1") (pintype "unspecified"))
    )
    (net (code "44") (name "Net-(D43-Pad1)") (class "Default")
      (node (ref "D43") (pin "1") (pinfunction "1_1") (pintype "unspecified"))
      (node (ref "SW44") (pin "1") (pinfunction "1_1") (pintype "unspecified"))
    )
    (net (code "45") (name "Net-(D44-Pad1)") (class "Default")
      (node (ref "D44") (pin "1") (pinfunction "1_1") (pintype "unspecified"))
      (node (ref "SW45") (pin "1") (pinfunction "1_1") (pintype "unspecified"))
    )
    (net (code "46") (name "Net-(D45-Pad1)") (class "Default")
      (node (ref "D45") (pin "1") (pinfunction "1_1") (pintype "unspecified"))
      (node (ref "SW50") (pin "1") (pinfunction "1_1") (pintype "unspecified"))
    )
    (net (code "47") (name "Net-(D46-Pad1)") (class "Default")
      (node (ref "D46") (pin "1") (pinfunction "1_1") (pintype "unspecified"))
      (node (ref "SW51") (pin "1") (pinfunction "1_1") (pintype "unspecified"))
    )
    (net (code "48") (name "Net-(D47-Pad1)") (class "Default")
      (node (ref "D47") (pin "1") (pinfunction "1_1") (pintype "unspecified"))
      (node (ref "SW52") (pin "1") (pinfunction "1_1") (pintype "unspecified"))
    )
    (net (code "49") (name "Net-(D48-Pad1)") (class "Default")
      (node (ref "D48") (pin "1") (pinfunction "1_1") (pintype "unspecified"))
      (node (ref "SW53") (pin "1") (pinfunction "1_1") (pintype "unspecified"))
    )
    (net (code "50") (name "Net-(D49-Pad1)") (class "Default")
      (node (ref "D49") (pin "1") (pinfunction "1_1") (pintype "unspecified"))
      (node (ref "SW54") (pin "1") (pinfunction "1_1") (pintype "unspecified"))
    )
    (net (code "51") (name "Net-(D50-Pad1)") (class "Default")
      (node (ref "D50") (pin "1") (pinfunction "1_1") (pintype "unspecified"))
      (node (ref "SW55") (pin "1") (pinfunction "1_1") (pintype "unspecified"))
    )
    (net (code "52") (name "Net-(D51-Pad1)") (class "Default")
      (node (ref "D51") (pin "1") (pinfunction "1_1") (pintype "unspecified"))
      (node (ref "SW61") (pin "1") (pinfunction "1_1") (pintype "unspecified"))
    )
    (net (code "53") (name "Net-(D52-Pad1)") (class "Default")
      (node (ref "D52") (pin "1") (pinfunction "1_1") (pintype "unspecified"))
      (node (ref "SW62") (pin "1") (pinfunction "1_1") (pintype "unspecified"))
    )
    (net (code "54") (name "Net-(D53-Pad1)") (class "Default")
      (node (ref "D53") (pin "1") (pinfunction "1_1") (pintype "unspecified"))
      (node (ref "SW63") (pin "1") (pinfunction "1_1") (pintype "unspecified"))
    )
    (net (code "55") (name "Net-(D54-Pad1)") (class "Default")
      (node (ref "D54") (pin "1") (pinfunction "1_1") (pintype "unspecified"))
      (node (ref "SW64") (pin "1") (pinfunction "1_1") (pintype "unspecified"))
    )
    (net (code "56") (name "Net-(D55-Pad1)") (class "Default")
      (node (ref "D55") (pin "1") (pinfunction "1_1") (pintype "unspecified"))
      (node (ref "SW65") (pin "1") (pinfunction "1_1") (pintype "unspecified"))
    )
    (net (code "57") (name "Net-(D56-Pad1)") (class "Default")
      (node (ref "D56") (pin "1") (pinfunction "1_1") (pintype "unspecified"))
      (node (ref "SW66") (pin "1") (pinfunction "1_1") (pintype "unspecified"))
    )
    (net (code "58") (name "Net-(D57-Pad1)") (class "Default")
      (node (ref "D57") (pin "1") (pinfunction "1_1") (pintype "unspecified"))
      (node (ref "SW70") (pin "1") (pinfunction "1_1") (pintype "unspecified"))
    )
    (net (code "59") (name "Net-(D58-Pad1)") (class "Default")
      (node (ref "D58") (pin "1") (pinfunction "1_1") (pintype "unspecified"))
      (node (ref "SW69") (pin "1") (pinfunction "1_1") (pintype "unspecified"))
    )
    (net (code "60") (name "Net-(D59-Pad1)") (class "Default")
      (node (ref "D59") (pin "1") (pinfunction "1_1") (pintype "unspecified"))
      (node (ref "SW68") (pin "1") (pinfunction "1_1") (pintype "unspecified"))
    )
    (net (code "61") (name "Net-(D60-Pad1)") (class "Default")
      (node (ref "D60") (pin "1") (pinfunction "1_1") (pintype "unspecified"))
      (node (ref "SW67") (pin "1") (pinfunction "1_1") (pintype "unspecified"))
    )
    (net (code "62") (name "Net-(D61-Pad1)") (class "Default")
      (node (ref "D61") (pin "1") (pinfunction "1_1") (pintype "unspecified"))
      (node (ref "SW41") (pin "1") (pinfunction "1_1") (pintype "unspecified"))
    )
    (net (code "63") (name "Net-(D62-Pad1)") (class "Default")
      (node (ref "D62") (pin "1") (pinfunction "1_1") (pintype "unspecified"))
      (node (ref "SW31") (pin "1") (pinfunction "1_1") (pintype "unspecified"))
    )
    (net (code "64") (name "Net-(D63-Pad1)") (class "Default")
      (node (ref "D63") (pin "1") (pinfunction "1_1") (pintype "unspecified"))
      (node (ref "SW30") (pin "1") (pinfunction "1_1") (pintype "unspecified"))
    )
    (net (code "65") (name "Net-(D64-Pad1)") (class "Default")
      (node (ref "D64") (pin "1") (pinfunction "1_1") (pintype "unspecified"))
      (node (ref "SW29") (pin "1") (pinfunction "1_1") (pintype "unspecified"))
    )
    (net (code "66") (name "Net-(D65-Pad1)") (class "Default")
      (node (ref "D65") (pin "1") (pinfunction "1_1") (pintype "unspecified"))
      (node (ref "SW28") (pin "1") (pinfunction "1_1") (pintype "unspecified"))
    )
    (net (code "67") (name "Net-(D66-Pad1)") (class "Default")
      (node (ref "D66") (pin "1") (pinfunction "1_1") (pintype "unspecified"))
      (node (ref "SW27") (pin "1") (pinfunction "1_1") (pintype "unspecified"))
    )
    (net (code "68") (name "Net-(D67-Pad1)") (class "Default")
      (node (ref "D67") (pin "1") (pinfunction "1_1") (pintype "unspecified"))
      (node (ref "SW17") (pin "1") (pinfunction "1_1") (pintype "unspecified"))
    )
    (net (code "69") (name "Net-(D68-Pad1)") (class "Default")
      (node (ref "D68") (pin "1") (pinfunction "1_1") (pintype "unspecified"))
      (node (ref "SW12") (pin "1") (pinfunction "1_1") (pintype "unspecified"))
    )
    (net (code "70") (name "Net-(D69-Pad1)") (class "Default")
      (node (ref "D69") (pin "1") (pinfunction "1_1") (pintype "unspecified"))
      (node (ref "SW11") (pin "1") (pinfunction "1_1") (pintype "unspecified"))
    )
    (net (code "71") (name "Net-(D70-Pad1)") (class "Default")
      (node (ref "D70") (pin "1") (pinfunction "1_1") (pintype "unspecified"))
      (node (ref "SW8") (pin "1") (pinfunction "1_1") (pintype "unspecified"))
    )
    (net (code "72") (name "Net-(D71-Pad1)") (class "Default")
      (node (ref "D71") (pin "1") (pinfunction "1_1") (pintype "unspecified"))
      (node (ref "SW9") (pin "1") (pinfunction "1_1") (pintype "unspecified"))
    )
    (net (code "73") (name "Net-(D72-Pad1)") (class "Default")
      (node (ref "D72") (pin "1") (pinfunction "1_1") (pintype "unspecified"))
      (node (ref "SW26") (pin "1") (pinfunction "1_1") (pintype "unspecified"))
    )
    (net (code "74") (name "Net-(D73-Pad1)") (class "Default")
      (node (ref "D73") (pin "1") (pinfunction "1_1") (pintype "unspecified"))
      (node (ref "SW16") (pin "1") (pinfunction "1_1") (pintype "unspecified"))
    )
    (net (code "75") (name "Net-(D74-Pad1)") (class "Default")
      (node (ref "D74") (pin "1") (pinfunction "1_1") (pintype "unspecified"))
      (node (ref "SW13") (pin "1") (pinfunction "1_1") (pintype "unspecified"))
    )
    (net (code "76") (name "Net-(D75-Pad1)") (class "Default")
      (node (ref "D75") (pin "1") (pinfunction "1_1") (pintype "unspecified"))
      (node (ref "SW10") (pin "1") (pinfunction "1_1") (pintype "unspecified"))
    )
    (net (code "77") (name "Net-(D76-Pad1)") (class "Default")
      (node (ref "D76") (pin "1") (pinfunction "1_1") (pintype "unspecified"))
      (node (ref "SW76") (pin "1") (pinfunction "1_1") (pintype "unspecified"))
    )
    (net (code "78") (name "Net-(D77-Pad1)") (class "Default")
      (node (ref "D77") (pin "1") (pinfunction "1_1") (pintype "unspecified"))
      (node (ref "SW77") (pin "1") (pinfunction "1_1") (pintype "unspecified"))
    )
    (net (code "79") (name "Net-(D78-Pad1)") (class "Default")
      (node (ref "D78") (pin "1") (pinfunction "1_1") (pintype "unspecified"))
      (node (ref "SW78") (pin "1") (pinfunction "1_1") (pintype "unspecified"))
    )
    (net (code "80") (name "Net-(D79-Pad1)") (class "Default")
      (node (ref "D79") (pin "1") (pinfunction "1_1") (pintype "unspecified"))
      (node (ref "SW79") (pin "1") (pinfunction "1_1") (pintype "unspecified"))
    )
    (net (code "81") (name "Net-(D80-Pad1)") (class "Default")
      (node (ref "D80") (pin "1") (pinfunction "1_1") (pintype "unspecified"))
      (node (ref "SW80") (pin "1") (pinfunction "1_1") (pintype "unspecified"))
    )
    (net (code "82") (name "Net-(MD1-2_VCC)") (class "Default")
      (node (ref "J1") (pin "2") (pinfunction "2_2") (pintype "unspecified"))
      (node (ref "MD1") (pin "2") (pinfunction "2_VCC_2") (pintype "unspecified"))
      (node (ref "MD1") (pin "8") (pinfunction "8_BLK_8") (pintype "unspecified"))
      (node (ref "U3") (pin "1") (pinfunction "VCC_1") (pintype "unspecified"))
      (node (ref "U4") (pin "1") (pinfunction "VCC_1") (pintype "unspecified"))
      (node (ref "U5") (pin "1") (pinfunction "VCC_1") (pintype "unspecified"))
      (node (ref "U6") (pin "1") (pinfunction "VCC_1") (pintype "unspecified"))
      (node (ref "U7") (pin "1") (pinfunction "5V0_1") (pintype "passive"))
    )
    (net (code "83") (name "Net-(MD1-3_SCL)") (class "Default")
      (node (ref "MD1") (pin "3") (pinfunction "3_SCL_3") (pintype "unspecified"))
      (node (ref "U2") (pin "15") (pinfunction "IO13_15") (pintype "unspecified"))
    )
    (net (code "84") (name "Net-(MD1-5_RST)") (class "Default")
      (node (ref "MD1") (pin "5") (pinfunction "5_RST_5") (pintype "unspecified"))
      (node (ref "U2") (pin "17") (pinfunction "D3_17") (pintype "unspecified"))
    )
    (net (code "85") (name "Net-(MD1-6_DC)") (class "Default")
      (node (ref "MD1") (pin "6") (pinfunction "6_DC_6") (pintype "unspecified"))
      (node (ref "U2") (pin "36") (pinfunction "D1_36") (pintype "unspecified"))
    )
    (net (code "86") (name "Net-(MD1-7_CS)") (class "Default")
      (node (ref "MD1") (pin "7") (pinfunction "7_CS_7") (pintype "unspecified"))
      (node (ref "U2") (pin "37") (pinfunction "D0_37") (pintype "unspecified"))
    )
    (net (code "87") (name "Net-(U1-QA)") (class "Default")
      (node (ref "D71") (pin "2") (pinfunction "2_2") (pintype "unspecified"))
      (node (ref "D72") (pin "2") (pinfunction "2_2") (pintype "unspecified"))
      (node (ref "D73") (pin "2") (pinfunction "2_2") (pintype "unspecified"))
      (node (ref "D74") (pin "2") (pinfunction "2_2") (pintype "unspecified"))
      (node (ref "D75") (pin "2") (pinfunction "2_2") (pintype "unspecified"))
      (node (ref "U1") (pin "15") (pinfunction "QA_15") (pintype "unspecified"))
    )
    (net (code "88") (name "Net-(U1-QB)") (class "Default")
      (node (ref "D1") (pin "2") (pinfunction "2_2") (pintype "unspecified"))
      (node (ref "D2") (pin "2") (pinfunction "2_2") (pintype "unspecified"))
      (node (ref "D3") (pin "2") (pinfunction "2_2") (pintype "unspecified"))
      (node (ref "D4") (pin "2") (pinfunction "2_2") (pintype "unspecified"))
      (node (ref "D5") (pin "2") (pinfunction "2_2") (pintype "unspecified"))
      (node (ref "U1") (pin "1") (pinfunction "QB_1") (pintype "unspecified"))
    )
    (net (code "89") (name "Net-(U1-QC)") (class "Default")
      (node (ref "D10") (pin "2") (pinfunction "2_2") (pintype "unspecified"))
      (node (ref "D6") (pin "2") (pinfunction "2_2") (pintype "unspecified"))
      (node (ref "D7") (pin "2") (pinfunction "2_2") (pintype "unspecified"))
      (node (ref "D8") (pin "2") (pinfunction "2_2") (pintype "unspecified"))
      (node (ref "D9") (pin "2") (pinfunction "2_2") (pintype "unspecified"))
      (node (ref "U1") (pin "2") (pinfunction "QC_2") (pintype "unspecified"))
    )
    (net (code "90") (name "Net-(U1-QD)") (class "Default")
      (node (ref "D11") (pin "2") (pinfunction "2_2") (pintype "unspecified"))
      (node (ref "D12") (pin "2") (pinfunction "2_2") (pintype "unspecified"))
      (node (ref "D13") (pin "2") (pinfunction "2_2") (pintype "unspecified"))
      (node (ref "D14") (pin "2") (pinfunction "2_2") (pintype "unspecified"))
      (node (ref "D15") (pin "2") (pinfunction "2_2") (pintype "unspecified"))
      (node (ref "U1") (pin "3") (pinfunction "QD_3") (pintype "unspecified"))
    )
    (net (code "91") (name "Net-(U1-QE)") (class "Default")
      (node (ref "D16") (pin "2") (pinfunction "2_2") (pintype "unspecified"))
      (node (ref "D17") (pin "2") (pinfunction "2_2") (pintype "unspecified"))
      (node (ref "D18") (pin "2") (pinfunction "2_2") (pintype "unspecified"))
      (node (ref "D19") (pin "2") (pinfunction "2_2") (pintype "unspecified"))
      (node (ref "D20") (pin "2") (pinfunction "2_2") (pintype "unspecified"))
      (node (ref "U1") (pin "4") (pinfunction "QE_4") (pintype "unspecified"))
    )
    (net (code "92") (name "Net-(U1-QF)") (class "Default")
      (node (ref "D21") (pin "2") (pinfunction "2_2") (pintype "unspecified"))
      (node (ref "D22") (pin "2") (pinfunction "2_2") (pintype "unspecified"))
      (node (ref "D23") (pin "2") (pinfunction "2_2") (pintype "unspecified"))
      (node (ref "D24") (pin "2") (pinfunction "2_2") (pintype "unspecified"))
      (node (ref "D25") (pin "2") (pinfunction "2_2") (pintype "unspecified"))
      (node (ref "U1") (pin "5") (pinfunction "QF_5") (pintype "unspecified"))
    )
    (net (code "93") (name "Net-(U1-QG)") (class "Default")
      (node (ref "D26") (pin "2") (pinfunction "2_2") (pintype "unspecified"))
      (node (ref "D27") (pin "2") (pinfunction "2_2") (pintype "unspecified"))
      (node (ref "D28") (pin "2") (pinfunction "2_2") (pintype "unspecified"))
      (node (ref "D29") (pin "2") (pinfunction "2_2") (pintype "unspecified"))
      (node (ref "D30") (pin "2") (pinfunction "2_2") (pintype "unspecified"))
      (node (ref "U1") (pin "6") (pinfunction "QG_6") (pintype "unspecified"))
    )
    (net (code "94") (name "Net-(U1-QH)") (class "Default")
      (node (ref "D31") (pin "2") (pinfunction "2_2") (pintype "unspecified"))
      (node (ref "D32") (pin "2") (pinfunction "2_2") (pintype "unspecified"))
      (node (ref "D33") (pin "2") (pinfunction "2_2") (pintype "unspecified"))
      (node (ref "D34") (pin "2") (pinfunction "2_2") (pintype "unspecified"))
      (node (ref "D35") (pin "2") (pinfunction "2_2") (pintype "unspecified"))
      (node (ref "U1") (pin "7") (pinfunction "QH_7") (pintype "unspecified"))
    )
    (net (code "95") (name "Net-(U1-RCLK)") (class "Default")
      (node (ref "U1") (pin "12") (pinfunction "RCLK_12") (pintype "unspecified"))
      (node (ref "U2") (pin "6") (pinfunction "IO35_6") (pintype "unspecified"))
    )
    (net (code "96") (name "Net-(U1-SER)") (class "Default")
      (node (ref "U1") (pin "14") (pinfunction "SER_14") (pintype "unspecified"))
      (node (ref "U2") (pin "5") (pinfunction "IO34_5") (pintype "unspecified"))
    )
    (net (code "97") (name "Net-(U1-SRCLK)") (class "Default")
      (node (ref "U1") (pin "11") (pinfunction "SRCLK_11") (pintype "unspecified"))
      (node (ref "U2") (pin "7") (pinfunction "IO32_7") (pintype "unspecified"))
    )
    (net (code "98") (name "Net-(U1-SRCLR#)") (class "Default")
      (node (ref "U1") (pin "10") (pinfunction "SRCLR#_10") (pintype "unspecified"))
      (node (ref "U1") (pin "16") (pinfunction "VCC_16") (pintype "unspecified"))
      (node (ref "U2") (pin "19") (pinfunction "5V_19") (pintype "unspecified"))
      (node (ref "U8") (pin "1") (pinfunction "1_1") (pintype "unspecified"))
      (node (ref "U9") (pin "10") (pinfunction "SRCLR#_10") (pintype "unspecified"))
      (node (ref "U9") (pin "16") (pinfunction "VCC_16") (pintype "unspecified"))
    )
    (net (code "99") (name "Net-(U2-GND-Pad20)") (class "Default")
      (node (ref "U2") (pin "20") (pinfunction "GND_20") (pintype "unspecified"))
      (node (ref "U7") (pin "3") (pinfunction "GND_3") (pintype "passive"))
    )
    (net (code "100") (name "Net-(U2-GND-Pad26)") (class "Default")
      (node (ref "U2") (pin "26") (pinfunction "GND_26") (pintype "unspecified"))
      (node (ref "U8") (pin "6") (pinfunction "6_6") (pintype "unspecified"))
    )
    (net (code "101") (name "Net-(U2-IO0)") (class "Default")
      (node (ref "U2") (pin "33") (pinfunction "IO0_33") (pintype "unspecified"))
      (node (ref "U8") (pin "3") (pinfunction "3_3") (pintype "unspecified"))
    )
    (net (code "102") (name "Net-(U2-IO2)") (class "Default")
      (node (ref "U2") (pin "34") (pinfunction "IO2_34") (pintype "unspecified"))
      (node (ref "U8") (pin "2") (pinfunction "2_2") (pintype "unspecified"))
    )
    (net (code "103") (name "Net-(U2-IO4)") (class "Default")
      (node (ref "U2") (pin "32") (pinfunction "IO4_32") (pintype "unspecified"))
      (node (ref "U8") (pin "4") (pinfunction "4_4") (pintype "unspecified"))
    )
    (net (code "104") (name "Net-(U2-IO5)") (class "Default")
      (node (ref "U2") (pin "29") (pinfunction "IO5_29") (pintype "unspecified"))
      (node (ref "U7") (pin "2") (pinfunction "Din_2") (pintype "input"))
    )
    (net (code "105") (name "Net-(U2-IO14)") (class "Default")
      (node (ref "U2") (pin "12") (pinfunction "IO14_12") (pintype "unspecified"))
      (node (ref "U9") (pin "11") (pinfunction "SRCLK_11") (pintype "unspecified"))
    )
    (net (code "106") (name "Net-(U2-IO15)") (class "Default")
      (node (ref "U2") (pin "35") (pinfunction "IO15_35") (pintype "unspecified"))
      (node (ref "U9") (pin "12") (pinfunction "RCLK_12") (pintype "unspecified"))
    )
    (net (code "107") (name "Net-(U2-IO16)") (class "Default")
      (node (ref "U2") (pin "31") (pinfunction "IO16_31") (pintype "unspecified"))
      (node (ref "U8") (pin "5") (pinfunction "5_5") (pintype "unspecified"))
    )
    (net (code "108") (name "Net-(U2-IO17)") (class "Default")
      (node (ref "U2") (pin "30") (pinfunction "IO17_30") (pintype "unspecified"))
      (node (ref "U9") (pin "14") (pinfunction "SER_14") (pintype "unspecified"))
    )
    (net (code "109") (name "Net-(U2-IO18)") (class "Default")
      (node (ref "SW10") (pin "2") (pinfunction "2_2") (pintype "unspecified"))
      (node (ref "SW11") (pin "2") (pinfunction "2_2") (pintype "unspecified"))
      (node (ref "SW19") (pin "2") (pinfunction "2_2") (pintype "unspecified"))
      (node (ref "SW2") (pin "2") (pinfunction "2_2") (pintype "unspecified"))
      (node (ref "SW22") (pin "2") (pinfunction "2_2") (pintype "unspecified"))
      (node (ref "SW29") (pin "2") (pinfunction "2_2") (pintype "unspecified"))
      (node (ref "SW39") (pin "2") (pinfunction "2_2") (pintype "unspecified"))
      (node (ref "SW43") (pin "2") (pinfunction "2_2") (pintype "unspecified"))
      (node (ref "SW46") (pin "2") (pinfunction "2_2") (pintype "unspecified"))
      (node (ref "SW47") (pin "2") (pinfunction "2_2") (pintype "unspecified"))
      (node (ref "SW54") (pin "2") (pinfunction "2_2") (pintype "unspecified"))
      (node (ref "SW59") (pin "2") (pinfunction "2_2") (pintype "unspecified"))
      (node (ref "SW62") (pin "2") (pinfunction "2_2") (pintype "unspecified"))
      (node (ref "SW69") (pin "2") (pinfunction "2_2") (pintype "unspecified"))
      (node (ref "SW74") (pin "2") (pinfunction "2_2") (pintype "unspecified"))
      (node (ref "SW77") (pin "2") (pinfunction "2_2") (pintype "unspecified"))
      (node (ref "U2") (pin "28") (pinfunction "IO18_28") (pintype "unspecified"))
    )
    (net (code "110") (name "Net-(U2-IO19)") (class "Default")
      (node (ref "SW12") (pin "2") (pinfunction "2_2") (pintype "unspecified"))
      (node (ref "SW13") (pin "2") (pinfunction "2_2") (pintype "unspecified"))
      (node (ref "SW18") (pin "2") (pinfunction "2_2") (pintype "unspecified"))
      (node (ref "SW23") (pin "2") (pinfunction "2_2") (pintype "unspecified"))
      (node (ref "SW3") (pin "2") (pinfunction "2_2") (pintype "unspecified"))
      (node (ref "SW30") (pin "2") (pinfunction "2_2") (pintype "unspecified"))
      (node (ref "SW34") (pin "2") (pinfunction "2_2") (pintype "unspecified"))
      (node (ref "SW35") (pin "2") (pinfunction "2_2") (pintype "unspecified"))
      (node (ref "SW38") (pin "2") (pinfunction "2_2") (pintype "unspecified"))
      (node (ref "SW44") (pin "2") (pinfunction "2_2") (pintype "unspecified"))
      (node (ref "SW53") (pin "2") (pinfunction "2_2") (pintype "unspecified"))
      (node (ref "SW58") (pin "2") (pinfunction "2_2") (pintype "unspecified"))
      (node (ref "SW63") (pin "2") (pinfunction "2_2") (pintype "unspecified"))
      (node (ref "SW68") (pin "2") (pinfunction "2_2") (pintype "unspecified"))
      (node (ref "SW73") (pin "2") (pinfunction "2_2") (pintype "unspecified"))
      (node (ref "SW78") (pin "2") (pinfunction "2_2") (pintype "unspecified"))
      (node (ref "U2") (pin "27") (pinfunction "IO19_27") (pintype "unspecified"))
    )
    (net (code "111") (name "Net-(U2-IO21)") (class "Default")
      (node (ref "SW1") (pin "2") (pinfunction "2_2") (pintype "unspecified"))
      (node (ref "SW20") (pin "2") (pinfunction "2_2") (pintype "unspecified"))
      (node (ref "SW21") (pin "2") (pinfunction "2_2") (pintype "unspecified"))
      (node (ref "SW28") (pin "2") (pinfunction "2_2") (pintype "unspecified"))
      (node (ref "SW40") (pin "2") (pinfunction "2_2") (pintype "unspecified"))
      (node (ref "SW42") (pin "2") (pinfunction "2_2") (pintype "unspecified"))
      (node (ref "SW48") (pin "2") (pinfunction "2_2") (pintype "unspecified"))
      (node (ref "SW49") (pin "2") (pinfunction "2_2") (pintype "unspecified"))
      (node (ref "SW55") (pin "2") (pinfunction "2_2") (pintype "unspecified"))
      (node (ref "SW60") (pin "2") (pinfunction "2_2") (pintype "unspecified"))
      (node (ref "SW61") (pin "2") (pinfunction "2_2") (pintype "unspecified"))
      (node (ref "SW70") (pin "2") (pinfunction "2_2") (pintype "unspecified"))
      (node (ref "SW75") (pin "2") (pinfunction "2_2") (pintype "unspecified"))
      (node (ref "SW76") (pin "2") (pinfunction "2_2") (pintype "unspecified"))
      (node (ref "SW8") (pin "2") (pinfunction "2_2") (pintype "unspecified"))
      (node (ref "SW9") (pin "2") (pinfunction "2_2") (pintype "unspecified"))
      (node (ref "U2") (pin "25") (pinfunction "IO21_25") (pintype "unspecified"))
    )
    (net (code "112") (name "Net-(U2-IO22)") (class "Default")
      (node (ref "SW15") (pin "2") (pinfunction "2_2") (pintype "unspecified"))
      (node (ref "SW16") (pin "2") (pinfunction "2_2") (pintype "unspecified"))
      (node (ref "SW17") (pin "2") (pinfunction "2_2") (pintype "unspecified"))
      (node (ref "SW24") (pin "2") (pinfunction "2_2") (pintype "unspecified"))
      (node (ref "SW31") (pin "2") (pinfunction "2_2") (pintype "unspecified"))
      (node (ref "SW32") (pin "2") (pinfunction "2_2") (pintype "unspecified"))
      (node (ref "SW33") (pin "2") (pinfunction "2_2") (pintype "unspecified"))
      (node (ref "SW37") (pin "2") (pinfunction "2_2") (pintype "unspecified"))
      (node (ref "SW4") (pin "2") (pinfunction "2_2") (pintype "unspecified"))
      (node (ref "SW45") (pin "2") (pinfunction "2_2") (pintype "unspecified"))
      (node (ref "SW52") (pin "2") (pinfunction "2_2") (pintype "unspecified"))
      (node (ref "SW57") (pin "2") (pinfunction "2_2") (pintype "unspecified"))
      (node (ref "SW64") (pin "2") (pinfunction "2_2") (pintype "unspecified"))
      (node (ref "SW67") (pin "2") (pinfunction "2_2") (pintype "unspecified"))
      (node (ref "SW72") (pin "2") (pinfunction "2_2") (pintype "unspecified"))
      (node (ref "SW79") (pin "2") (pinfunction "2_2") (pintype "unspecified"))
      (node (ref "U2") (pin "22") (pinfunction "IO22_22") (pintype "unspecified"))
    )
    (net (code "113") (name "Net-(U2-IO23)") (class "Default")
      (node (ref "SW14") (pin "2") (pinfunction "2_2") (pintype "unspecified"))
      (node (ref "SW25") (pin "2") (pinfunction "2_2") (pintype "unspecified"))
      (node (ref "SW26") (pin "2") (pinfunction "2_2") (pintype "unspecified"))
      (node (ref "SW27") (pin "2") (pinfunction "2_2") (pintype "unspecified"))
      (node (ref "SW36") (pin "2") (pinfunction "2_2") (pintype "unspecified"))
      (node (ref "SW41") (pin "2") (pinfunction "2_2") (pintype "unspecified"))
      (node (ref "SW5") (pin "2") (pinfunction "2_2") (pintype "unspecified"))
      (node (ref "SW50") (pin "2") (pinfunction "2_2") (pintype "unspecified"))
      (node (ref "SW51") (pin "2") (pinfunction "2_2") (pintype "unspecified"))
      (node (ref "SW56") (pin "2") (pinfunction "2_2") (pintype "unspecified"))
      (node (ref "SW6") (pin "2") (pinfunction "2_2") (pintype "unspecified"))
      (node (ref "SW65") (pin "2") (pinfunction "2_2") (pintype "unspecified"))
      (node (ref "SW66") (pin "2") (pinfunction "2_2") (pintype "unspecified"))
      (node (ref "SW7") (pin "2") (pinfunction "2_2") (pintype "unspecified"))
      (node (ref "SW71") (pin "2") (pinfunction "2_2") (pintype "unspecified"))
      (node (ref "SW80") (pin "2") (pinfunction "2_2") (pintype "unspecified"))
      (node (ref "U2") (pin "21") (pinfunction "IO23_21") (pintype "unspecified"))
    )
    (net (code "114") (name "Net-(U2-IO25)") (class "Default")
      (node (ref "U2") (pin "9") (pinfunction "IO25_9") (pintype "unspecified"))
      (node (ref "U3") (pin "3") (pinfunction "OUT_3") (pintype "unspecified"))
    )
    (net (code "115") (name "Net-(U2-IO26)") (class "Default")
      (node (ref "U2") (pin "10") (pinfunction "IO26_10") (pintype "unspecified"))
      (node (ref "U5") (pin "3") (pinfunction "OUT_3") (pintype "unspecified"))
    )
    (net (code "116") (name "Net-(U2-IO27)") (class "Default")
      (node (ref "U2") (pin "11") (pinfunction "IO27_11") (pintype "unspecified"))
      (node (ref "U6") (pin "3") (pinfunction "OUT_3") (pintype "unspecified"))
    )
    (net (code "117") (name "Net-(U2-IO33)") (class "Default")
      (node (ref "U2") (pin "8") (pinfunction "IO33_8") (pintype "unspecified"))
      (node (ref "U4") (pin "3") (pinfunction "OUT_3") (pintype "unspecified"))
    )
    (net (code "118") (name "Net-(U3-GND)") (class "Default")
      (node (ref "U3") (pin "2") (pinfunction "GND_2") (pintype "unspecified"))
      (node (ref "U4") (pin "2") (pinfunction "GND_2") (pintype "unspecified"))
      (node (ref "U5") (pin "2") (pinfunction "GND_2") (pintype "unspecified"))
      (node (ref "U6") (pin "2") (pinfunction "GND_2") (pintype "unspecified"))
    )
    (net (code "119") (name "Net-(U9-QA)") (class "Default")
      (node (ref "D76") (pin "2") (pinfunction "2_2") (pintype "unspecified"))
      (node (ref "D77") (pin "2") (pinfunction "2_2") (pintype "unspecified"))
      (node (ref "D78") (pin "2") (pinfunction "2_2") (pintype "unspecified"))
      (node (ref "D79") (pin "2") (pinfunction "2_2") (pintype "unspecified"))
      (node (ref "D80") (pin "2") (pinfunction "2_2") (pintype "unspecified"))
      (node (ref "U9") (pin "15") (pinfunction "QA_15") (pintype "unspecified"))
    )
    (net (code "120") (name "Net-(U9-QB)") (class "Default")
      (node (ref "D66") (pin "2") (pinfunction "2_2") (pintype "unspecified"))
      (node (ref "D67") (pin "2") (pinfunction "2_2") (pintype "unspecified"))
      (node (ref "D68") (pin "2") (pinfunction "2_2") (pintype "unspecified"))
      (node (ref "D69") (pin "2") (pinfunction "2_2") (pintype "unspecified"))
      (node (ref "D70") (pin "2") (pinfunction "2_2") (pintype "unspecified"))
      (node (ref "U9") (pin "1") (pinfunction "QB_1") (pintype "unspecified"))
    )
    (net (code "121") (name "Net-(U9-QC)") (class "Default")
      (node (ref "D61") (pin "2") (pinfunction "2_2") (pintype "unspecified"))
      (node (ref "D62") (pin "2") (pinfunction "2_2") (pintype "unspecified"))
      (node (ref "D63") (pin "2") (pinfunction "2_2") (pintype "unspecified"))
      (node (ref "D64") (pin "2") (pinfunction "2_2") (pintype "unspecified"))
      (node (ref "D65") (pin "2") (pinfunction "2_2") (pintype "unspecified"))
      (node (ref "U9") (pin "2") (pinfunction "QC_2") (pintype "unspecified"))
    )
    (net (code "122") (name "Net-(U9-QD)") (class "Default")
      (node (ref "D56") (pin "2") (pinfunction "2_2") (pintype "unspecified"))
      (node (ref "D57") (pin "2") (pinfunction "2_2") (pintype "unspecified"))
      (node (ref "D58") (pin "2") (pinfunction "2_2") (pintype "unspecified"))
      (node (ref "D59") (pin "2") (pinfunction "2_2") (pintype "unspecified"))
      (node (ref "D60") (pin "2") (pinfunction "2_2") (pintype "unspecified"))
      (node (ref "U9") (pin "3") (pinfunction "QD_3") (pintype "unspecified"))
    )
    (net (code "123") (name "Net-(U9-QE)") (class "Default")
      (node (ref "D51") (pin "2") (pinfunction "2_2") (pintype "unspecified"))
      (node (ref "D52") (pin "2") (pinfunction "2_2") (pintype "unspecified"))
      (node (ref "D53") (pin "2") (pinfunction "2_2") (pintype "unspecified"))
      (node (ref "D54") (pin "2") (pinfunction "2_2") (pintype "unspecified"))
      (node (ref "D55") (pin "2") (pinfunction "2_2") (pintype "unspecified"))
      (node (ref "U9") (pin "4") (pinfunction "QE_4") (pintype "unspecified"))
    )
    (net (code "124") (name "Net-(U9-QF)") (class "Default")
      (node (ref "D46") (pin "2") (pinfunction "2_2") (pintype "unspecified"))
      (node (ref "D47") (pin "2") (pinfunction "2_2") (pintype "unspecified"))
      (node (ref "D48") (pin "2") (pinfunction "2_2") (pintype "unspecified"))
      (node (ref "D49") (pin "2") (pinfunction "2_2") (pintype "unspecified"))
      (node (ref "D50") (pin "2") (pinfunction "2_2") (pintype "unspecified"))
      (node (ref "U9") (pin "5") (pinfunction "QF_5") (pintype "unspecified"))
    )
    (net (code "125") (name "Net-(U9-QG)") (class "Default")
      (node (ref "D41") (pin "2") (pinfunction "2_2") (pintype "unspecified"))
      (node (ref "D42") (pin "2") (pinfunction "2_2") (pintype "unspecified"))
      (node (ref "D43") (pin "2") (pinfunction "2_2") (pintype "unspecified"))
      (node (ref "D44") (pin "2") (pinfunction "2_2") (pintype "unspecified"))
      (node (ref "D45") (pin "2") (pinfunction "2_2") (pintype "unspecified"))
      (node (ref "U9") (pin "6") (pinfunction "QG_6") (pintype "unspecified"))
    )
    (net (code "126") (name "Net-(U9-QH)") (class "Default")
      (node (ref "D36") (pin "2") (pinfunction "2_2") (pintype "unspecified"))
      (node (ref "D37") (pin "2") (pinfunction "2_2") (pintype "unspecified"))
      (node (ref "D38") (pin "2") (pinfunction "2_2") (pintype "unspecified"))
      (node (ref "D39") (pin "2") (pinfunction "2_2") (pintype "unspecified"))
      (node (ref "D40") (pin "2") (pinfunction "2_2") (pintype "unspecified"))
      (node (ref "U9") (pin "7") (pinfunction "QH_7") (pintype "unspecified"))
    )
    (net (code "127") (name "unconnected-(U1-QH&apos;-Pad9)") (class "Default")
      (node (ref "U1") (pin "9") (pinfunction "QH&apos;_9") (pintype "unspecified"))
    )
    (net (code "128") (name "unconnected-(U2-3V3-Pad1)") (class "Default")
      (node (ref "U2") (pin "1") (pinfunction "3V3_1") (pintype "unspecified"))
    )
    (net (code "129") (name "unconnected-(U2-CLK-Pad38)") (class "Default")
      (node (ref "U2") (pin "38") (pinfunction "CLK_38") (pintype "unspecified"))
    )
    (net (code "130") (name "unconnected-(U2-CMD-Pad18)") (class "Default")
      (node (ref "U2") (pin "18") (pinfunction "CMD_18") (pintype "unspecified"))
    )
    (net (code "131") (name "unconnected-(U2-EN-Pad2)") (class "Default")
      (node (ref "U2") (pin "2") (pinfunction "EN_2") (pintype "unspecified"))
    )
    (net (code "132") (name "unconnected-(U2-IO12-Pad13)") (class "Default")
      (node (ref "U2") (pin "13") (pinfunction "IO12_13") (pintype "unspecified"))
    )
    (net (code "133") (name "unconnected-(U2-RX-Pad24)") (class "Default")
      (node (ref "U2") (pin "24") (pinfunction "RX_24") (pintype "unspecified"))
    )
    (net (code "134") (name "unconnected-(U2-TX-Pad23)") (class "Default")
      (node (ref "U2") (pin "23") (pinfunction "TX_23") (pintype "unspecified"))
    )
    (net (code "135") (name "unconnected-(U2-VN-Pad4)") (class "Default")
      (node (ref "U2") (pin "4") (pinfunction "VN_4") (pintype "unspecified"))
    )
    (net (code "136") (name "unconnected-(U2-VP-Pad3)") (class "Default")
      (node (ref "U2") (pin "3") (pinfunction "VP_3") (pintype "unspecified"))
    )
    (net (code "137") (name "unconnected-(U7-5V0-Pad4)") (class "Default")
      (node (ref "U7") (pin "4") (pinfunction "5V0_4") (pintype "passive"))
    )
    (net (code "138") (name "unconnected-(U7-Dout-Pad5)") (class "Default")
      (node (ref "U7") (pin "5") (pinfunction "Dout_5") (pintype "output"))
    )
    (net (code "139") (name "unconnected-(U7-GND-Pad6)") (class "Default")
      (node (ref "U7") (pin "6") (pinfunction "GND_6") (pintype "passive"))
    )
    (net (code "140") (name "unconnected-(U9-QH&apos;-Pad9)") (class "Default")
      (node (ref "U9") (pin "9") (pinfunction "QH&apos;_9") (pintype "unspecified"))
    )
  )
)
